# CMM_MACHINE.net
KiCad netlist of a schematic drawn in Altium Designer
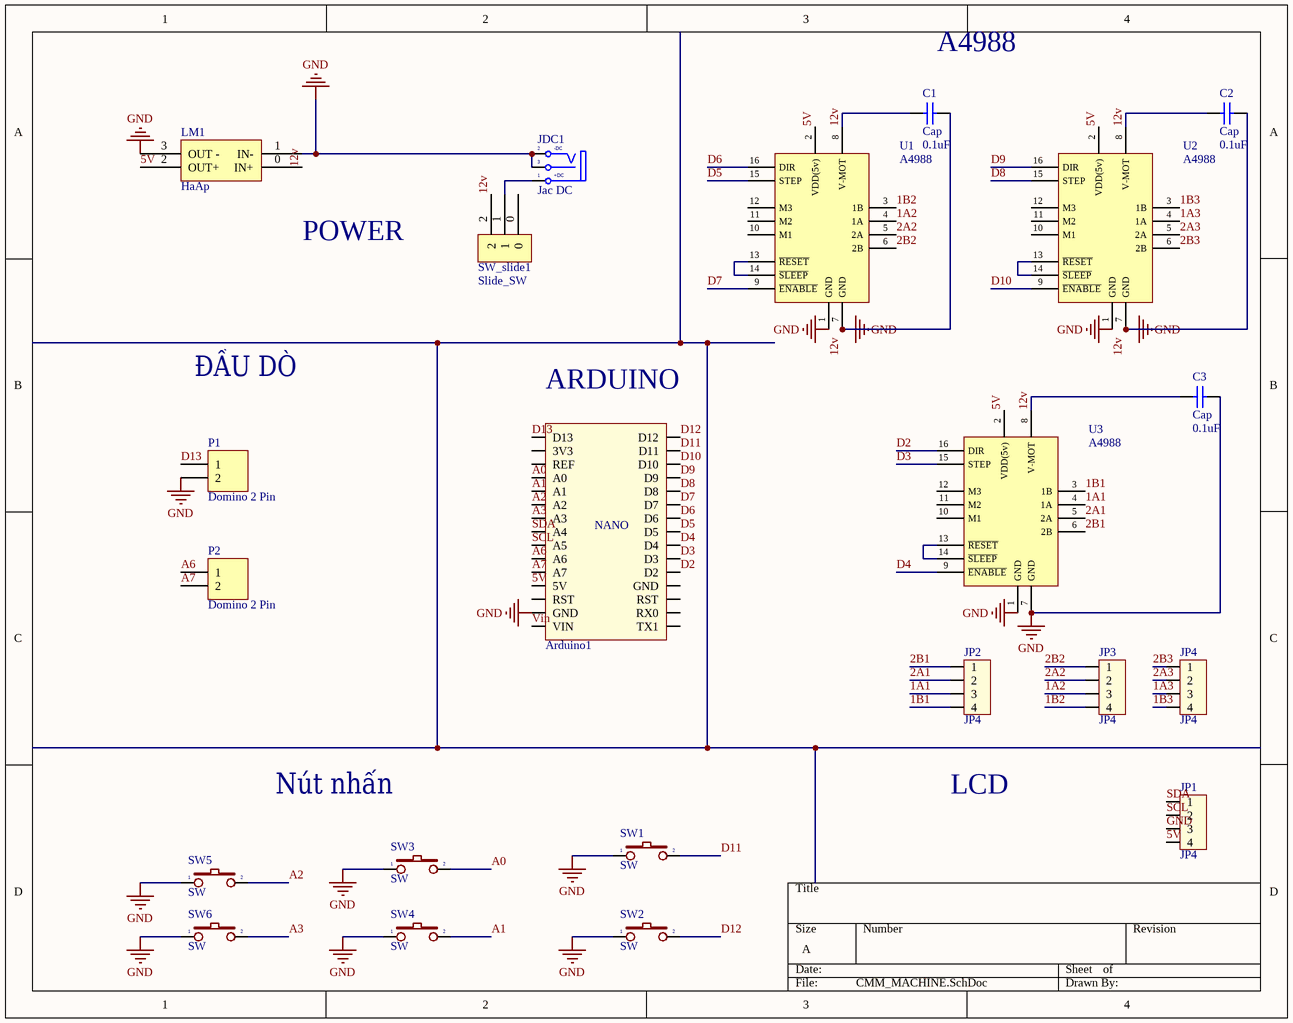
[diagram p0: CMM_MACHINE.SchDoc]

(export (version "E")
  (design (tool "Eeschema 10.0.6"))
  (components
    (comp (ref "Arduino1")
      (value "Arduino Nano")
      (footprint "Arduino Nano")
      (description "Arduino NANO")
      (libsource (lib "TechMT.VN_Lib_Project v2") (part "Arduino Nano"))
    )
    (comp (ref "C1")
      (value "Cap")
      (footprint "C3MM")
      (description "Capacitor")
      (fields (field (name "ALTIUM_VALUE") "0.1uF") (field (name "PUBLISHER") "Altium Limited"))
      (libsource (lib "hphonglib") (part "Cap"))
    )
    (comp (ref "C2")
      (value "Cap")
      (footprint "C3MM")
      (description "Capacitor")
      (fields (field (name "ALTIUM_VALUE") "0.1uF") (field (name "PUBLISHER") "Altium Limited"))
      (libsource (lib "hphonglib") (part "Cap"))
    )
    (comp (ref "C3")
      (value "Cap")
      (footprint "C3MM")
      (description "Capacitor")
      (fields (field (name "ALTIUM_VALUE") "0.1uF") (field (name "PUBLISHER") "Altium Limited"))
      (libsource (lib "hphonglib") (part "Cap"))
    )
    (comp (ref "JDC1")
      (value "Jac DC")
      (footprint "DC0")
      (description "Jac DC input")
      (libsource (lib "TechMT.VN_Lib_Project v2") (part "DCIN"))
    )
    (comp (ref "JP1")
      (value "JP4")
      (footprint "CON4")
      (description "Connector 4")
      (libsource (lib "hphonglib") (part "Con4"))
    )
    (comp (ref "JP2")
      (value "JP4")
      (footprint "CON4")
      (description "Connector 4")
      (libsource (lib "My Library") (part "Con4"))
    )
    (comp (ref "JP3")
      (value "JP4")
      (footprint "CON4")
      (description "Connector 4")
      (libsource (lib "My Library") (part "Con4"))
    )
    (comp (ref "JP4")
      (value "JP4")
      (footprint "CON4")
      (description "Connector 4")
      (libsource (lib "My Library") (part "Con4"))
    )
    (comp (ref "LM1")
      (value "HaAp")
      (footprint "BUCK_LM2596")
      (libsource (lib "BUCK_LM2596") (part "BUCK_LM2596"))
    )
    (comp (ref "P1")
      (value "Domino 2 Pin")
      (footprint "DOMINO_2PIN_5.08mm")
      (libsource (lib "MinhTien_SCHLib") (part "Domino 2 pin"))
    )
    (comp (ref "P2")
      (value "Domino 2 Pin")
      (footprint "DOMINO_2PIN_5.08mm")
      (libsource (lib "MinhTien_SCHLib") (part "Domino 2 pin"))
    )
    (comp (ref "SW1")
      (value "SW")
      (footprint "SW2")
      (description "Switch button 2 pin")
      (libsource (lib "hphonglib") (part "SW2"))
    )
    (comp (ref "SW2")
      (value "SW")
      (footprint "SW2")
      (description "Switch button 2 pin")
      (libsource (lib "hphonglib") (part "SW2"))
    )
    (comp (ref "SW3")
      (value "SW")
      (footprint "SW2")
      (description "Switch button 2 pin")
      (libsource (lib "hphonglib") (part "SW2"))
    )
    (comp (ref "SW4")
      (value "SW")
      (footprint "SW2")
      (description "Switch button 2 pin")
      (libsource (lib "hphonglib") (part "SW2"))
    )
    (comp (ref "SW5")
      (value "SW")
      (footprint "SW2")
      (description "Switch button 2 pin")
      (libsource (lib "hphonglib") (part "SW2"))
    )
    (comp (ref "SW6")
      (value "SW")
      (footprint "SW2")
      (description "Switch button 2 pin")
      (libsource (lib "hphonglib") (part "SW2"))
    )
    (comp (ref "SW_slide1")
      (value "Slide_SW")
      (footprint "Slide_SW")
      (libsource (lib "Cong_tac_truot") (part "Slide_SW"))
    )
    (comp (ref "U1")
      (value "A4988")
      (footprint "A4988(driver)")
      (libsource (lib "My Library") (part "A4988"))
    )
    (comp (ref "U2")
      (value "A4988")
      (footprint "A4988(driver)")
      (libsource (lib "My Library") (part "A4988"))
    )
    (comp (ref "U3")
      (value "A4988")
      (footprint "A4988(driver)")
      (libsource (lib "My Library") (part "A4988"))
    )
  )
  (nets
    (net (code "1") (name "/1A1") (class "Default")
      (node (ref "JP2") (pin "3") (pinfunction "3_3") (pintype "passive"))
      (node (ref "U3") (pin "4") (pinfunction "1A_4") (pintype "power_in"))
    )
    (net (code "2") (name "/1A2") (class "Default")
      (node (ref "JP3") (pin "3") (pinfunction "3_3") (pintype "passive"))
      (node (ref "U1") (pin "4") (pinfunction "1A_4") (pintype "power_in"))
    )
    (net (code "3") (name "/1A3") (class "Default")
      (node (ref "JP4") (pin "3") (pinfunction "3_3") (pintype "passive"))
      (node (ref "U2") (pin "4") (pinfunction "1A_4") (pintype "power_in"))
    )
    (net (code "4") (name "/1B1") (class "Default")
      (node (ref "JP2") (pin "4") (pinfunction "4_4") (pintype "passive"))
      (node (ref "U3") (pin "3") (pinfunction "1B_3") (pintype "power_in"))
    )
    (net (code "5") (name "/1B2") (class "Default")
      (node (ref "JP3") (pin "4") (pinfunction "4_4") (pintype "passive"))
      (node (ref "U1") (pin "3") (pinfunction "1B_3") (pintype "power_in"))
    )
    (net (code "6") (name "/1B3") (class "Default")
      (node (ref "JP4") (pin "4") (pinfunction "4_4") (pintype "passive"))
      (node (ref "U2") (pin "3") (pinfunction "1B_3") (pintype "power_in"))
    )
    (net (code "7") (name "/2A1") (class "Default")
      (node (ref "JP2") (pin "2") (pinfunction "2_2") (pintype "passive"))
      (node (ref "U3") (pin "5") (pinfunction "2A_5") (pintype "power_in"))
    )
    (net (code "8") (name "/2A2") (class "Default")
      (node (ref "JP3") (pin "2") (pinfunction "2_2") (pintype "passive"))
      (node (ref "U1") (pin "5") (pinfunction "2A_5") (pintype "power_in"))
    )
    (net (code "9") (name "/2A3") (class "Default")
      (node (ref "JP4") (pin "2") (pinfunction "2_2") (pintype "passive"))
      (node (ref "U2") (pin "5") (pinfunction "2A_5") (pintype "power_in"))
    )
    (net (code "10") (name "/2B1") (class "Default")
      (node (ref "JP2") (pin "1") (pinfunction "1_1") (pintype "passive"))
      (node (ref "U3") (pin "6") (pinfunction "2B_6") (pintype "power_in"))
    )
    (net (code "11") (name "/2B2") (class "Default")
      (node (ref "JP3") (pin "1") (pinfunction "1_1") (pintype "passive"))
      (node (ref "U1") (pin "6") (pinfunction "2B_6") (pintype "power_in"))
    )
    (net (code "12") (name "/2B3") (class "Default")
      (node (ref "JP4") (pin "1") (pinfunction "1_1") (pintype "passive"))
      (node (ref "U2") (pin "6") (pinfunction "2B_6") (pintype "power_in"))
    )
    (net (code "13") (name "/5V") (class "Default")
      (node (ref "Arduino1") (pin "5V") (pinfunction "5V_5V") (pintype "passive"))
      (node (ref "JP1") (pin "4") (pinfunction "4_4") (pintype "passive"))
      (node (ref "LM1") (pin "2") (pinfunction "OUT+_2") (pintype "passive"))
      (node (ref "U1") (pin "2") (pinfunction "VDD(5v)_2") (pintype "power_in"))
      (node (ref "U2") (pin "2") (pinfunction "VDD(5v)_2") (pintype "power_in"))
      (node (ref "U3") (pin "2") (pinfunction "VDD(5v)_2") (pintype "power_in"))
    )
    (net (code "14") (name "/12v") (class "Default")
      (node (ref "C1") (pin "2") (pinfunction "2_2") (pintype "passive"))
      (node (ref "C2") (pin "2") (pinfunction "2_2") (pintype "passive"))
      (node (ref "C3") (pin "2") (pinfunction "2_2") (pintype "passive"))
      (node (ref "LM1") (pin "0") (pinfunction "IN+_0") (pintype "passive"))
      (node (ref "SW_slide1") (pin "2") (pinfunction "2_2") (pintype "passive"))
      (node (ref "U1") (pin "8") (pinfunction "V-MOT_8") (pintype "power_in"))
      (node (ref "U2") (pin "8") (pinfunction "V-MOT_8") (pintype "power_in"))
      (node (ref "U3") (pin "8") (pinfunction "V-MOT_8") (pintype "power_in"))
    )
    (net (code "15") (name "/A0") (class "Default")
      (node (ref "Arduino1") (pin "A0") (pinfunction "A0_A0") (pintype "passive"))
      (node (ref "SW3") (pin "2") (pinfunction "2_2") (pintype "passive"))
    )
    (net (code "16") (name "/A1") (class "Default")
      (node (ref "Arduino1") (pin "A1") (pinfunction "A1_A1") (pintype "passive"))
      (node (ref "SW4") (pin "2") (pinfunction "2_2") (pintype "passive"))
    )
    (net (code "17") (name "/A2") (class "Default")
      (node (ref "Arduino1") (pin "A2") (pinfunction "A2_A2") (pintype "passive"))
      (node (ref "SW5") (pin "2") (pinfunction "2_2") (pintype "passive"))
    )
    (net (code "18") (name "/A3") (class "Default")
      (node (ref "Arduino1") (pin "A3") (pinfunction "A3_A3") (pintype "passive"))
      (node (ref "SW6") (pin "2") (pinfunction "2_2") (pintype "passive"))
    )
    (net (code "19") (name "/A6") (class "Default")
      (node (ref "Arduino1") (pin "A6") (pinfunction "A6_A6") (pintype "passive"))
      (node (ref "P2") (pin "1") (pinfunction "1_1") (pintype "passive"))
    )
    (net (code "20") (name "/A7") (class "Default")
      (node (ref "Arduino1") (pin "A7") (pinfunction "A7_A7") (pintype "passive"))
      (node (ref "P2") (pin "2") (pinfunction "2_2") (pintype "passive"))
    )
    (net (code "21") (name "/D2") (class "Default")
      (node (ref "Arduino1") (pin "D2") (pinfunction "D2_D2") (pintype "passive"))
      (node (ref "U3") (pin "16") (pinfunction "DIR_16") (pintype "power_in"))
    )
    (net (code "22") (name "/D3") (class "Default")
      (node (ref "Arduino1") (pin "D3") (pinfunction "D3_D3") (pintype "passive"))
      (node (ref "U3") (pin "15") (pinfunction "STEP_15") (pintype "power_in"))
    )
    (net (code "23") (name "/D4") (class "Default")
      (node (ref "Arduino1") (pin "D4") (pinfunction "D4_D4") (pintype "passive"))
      (node (ref "U3") (pin "9") (pinfunction "~{ENABLE}_9") (pintype "power_in"))
    )
    (net (code "24") (name "/D5") (class "Default")
      (node (ref "Arduino1") (pin "D5") (pinfunction "D5_D5") (pintype "passive"))
      (node (ref "U1") (pin "15") (pinfunction "STEP_15") (pintype "power_in"))
    )
    (net (code "25") (name "/D6") (class "Default")
      (node (ref "Arduino1") (pin "D6") (pinfunction "D6_D6") (pintype "passive"))
      (node (ref "U1") (pin "16") (pinfunction "DIR_16") (pintype "power_in"))
    )
    (net (code "26") (name "/D7") (class "Default")
      (node (ref "Arduino1") (pin "D7") (pinfunction "D7_D7") (pintype "passive"))
      (node (ref "U1") (pin "9") (pinfunction "~{ENABLE}_9") (pintype "power_in"))
    )
    (net (code "27") (name "/D8") (class "Default")
      (node (ref "Arduino1") (pin "D8") (pinfunction "D8_D8") (pintype "passive"))
      (node (ref "U2") (pin "15") (pinfunction "STEP_15") (pintype "power_in"))
    )
    (net (code "28") (name "/D9") (class "Default")
      (node (ref "Arduino1") (pin "D9") (pinfunction "D9_D9") (pintype "passive"))
      (node (ref "U2") (pin "16") (pinfunction "DIR_16") (pintype "power_in"))
    )
    (net (code "29") (name "/D10") (class "Default")
      (node (ref "Arduino1") (pin "D10") (pinfunction "D10_D10") (pintype "passive"))
      (node (ref "U2") (pin "9") (pinfunction "~{ENABLE}_9") (pintype "power_in"))
    )
    (net (code "30") (name "/D11") (class "Default")
      (node (ref "Arduino1") (pin "D11") (pinfunction "D11_D11") (pintype "passive"))
      (node (ref "SW1") (pin "2") (pinfunction "2_2") (pintype "passive"))
    )
    (net (code "31") (name "/D12") (class "Default")
      (node (ref "Arduino1") (pin "D12") (pinfunction "D12_D12") (pintype "passive"))
      (node (ref "SW2") (pin "2") (pinfunction "2_2") (pintype "passive"))
    )
    (net (code "32") (name "/D13") (class "Default")
      (node (ref "Arduino1") (pin "D13") (pinfunction "D13_D13") (pintype "passive"))
      (node (ref "P1") (pin "1") (pinfunction "1_1") (pintype "passive"))
    )
    (net (code "33") (name "/SCL") (class "Default")
      (node (ref "Arduino1") (pin "A5") (pinfunction "A5_A5") (pintype "passive"))
      (node (ref "JP1") (pin "2") (pinfunction "2_2") (pintype "passive"))
    )
    (net (code "34") (name "/SDA") (class "Default")
      (node (ref "Arduino1") (pin "A4") (pinfunction "A4_A4") (pintype "passive"))
      (node (ref "JP1") (pin "1") (pinfunction "1_1") (pintype "passive"))
    )
    (net (code "35") (name "/Vin") (class "Default")
      (node (ref "Arduino1") (pin "VIN") (pinfunction "VIN_VIN") (pintype "passive"))
    )
    (net (code "36") (name "GND") (class "Default")
      (node (ref "Arduino1") (pin "GND") (pinfunction "GND_GND") (pintype "passive"))
      (node (ref "C1") (pin "1") (pinfunction "1_1") (pintype "passive"))
      (node (ref "C2") (pin "1") (pinfunction "1_1") (pintype "passive"))
      (node (ref "C3") (pin "1") (pinfunction "1_1") (pintype "passive"))
      (node (ref "JDC1") (pin "2") (pinfunction "TN_2") (pintype "passive"))
      (node (ref "JDC1") (pin "3") (pinfunction "S_3") (pintype "power_in"))
      (node (ref "JP1") (pin "3") (pinfunction "3_3") (pintype "passive"))
      (node (ref "LM1") (pin "1") (pinfunction "IN-_1") (pintype "passive"))
      (node (ref "LM1") (pin "3") (pinfunction "OUT_-_3") (pintype "passive"))
      (node (ref "P1") (pin "2") (pinfunction "2_2") (pintype "passive"))
      (node (ref "SW1") (pin "1") (pinfunction "1_1") (pintype "passive"))
      (node (ref "SW2") (pin "1") (pinfunction "1_1") (pintype "passive"))
      (node (ref "SW3") (pin "1") (pinfunction "1_1") (pintype "passive"))
      (node (ref "SW4") (pin "1") (pinfunction "1_1") (pintype "passive"))
      (node (ref "SW5") (pin "1") (pinfunction "1_1") (pintype "passive"))
      (node (ref "SW6") (pin "1") (pinfunction "1_1") (pintype "passive"))
      (node (ref "U1") (pin "1") (pinfunction "GND_1") (pintype "power_in"))
      (node (ref "U1") (pin "7") (pinfunction "GND_7") (pintype "power_in"))
      (node (ref "U2") (pin "1") (pinfunction "GND_1") (pintype "power_in"))
      (node (ref "U2") (pin "7") (pinfunction "GND_7") (pintype "power_in"))
      (node (ref "U3") (pin "1") (pinfunction "GND_1") (pintype "power_in"))
      (node (ref "U3") (pin "7") (pinfunction "GND_7") (pintype "power_in"))
    )
    (net (code "37") (name "Net-(JDC1-T)") (class "Default")
      (node (ref "JDC1") (pin "1") (pinfunction "T_1") (pintype "passive"))
      (node (ref "SW_slide1") (pin "1") (pinfunction "1_1") (pintype "passive"))
    )
    (net (code "38") (name "Net-(U1-~{RESET})") (class "Default")
      (node (ref "U1") (pin "13") (pinfunction "~{RESET}_13") (pintype "power_in"))
      (node (ref "U1") (pin "14") (pinfunction "~{SLEEP}_14") (pintype "power_in"))
    )
    (net (code "39") (name "Net-(U2-~{RESET})") (class "Default")
      (node (ref "U2") (pin "13") (pinfunction "~{RESET}_13") (pintype "power_in"))
      (node (ref "U2") (pin "14") (pinfunction "~{SLEEP}_14") (pintype "power_in"))
    )
    (net (code "40") (name "Net-(U3-~{RESET})") (class "Default")
      (node (ref "U3") (pin "13") (pinfunction "~{RESET}_13") (pintype "power_in"))
      (node (ref "U3") (pin "14") (pinfunction "~{SLEEP}_14") (pintype "power_in"))
    )
    (net (code "41") (name "unconnected-(Arduino1-Pad3V3)") (class "Default")
      (node (ref "Arduino1") (pin "3V3") (pinfunction "3V3_3V3") (pintype "passive"))
    )
    (net (code "42") (name "unconnected-(Arduino1-PadGND)") (class "Default")
      (node (ref "Arduino1") (pin "GND") (pinfunction "GND_GND") (pintype "passive"))
    )
    (net (code "43") (name "unconnected-(Arduino1-PadREF)") (class "Default")
      (node (ref "Arduino1") (pin "REF") (pinfunction "REF_REF") (pintype "passive"))
    )
    (net (code "44") (name "unconnected-(Arduino1-PadRST)") (class "Default")
      (node (ref "Arduino1") (pin "RST") (pinfunction "RST_RST") (pintype "passive"))
    )
    (net (code "45") (name "unconnected-(Arduino1-PadRST)_1") (class "Default")
      (node (ref "Arduino1") (pin "RST") (pinfunction "RST_RST") (pintype "passive"))
    )
    (net (code "46") (name "unconnected-(Arduino1-PadRX0)") (class "Default")
      (node (ref "Arduino1") (pin "RX0") (pinfunction "RX0_RX0") (pintype "passive"))
    )
    (net (code "47") (name "unconnected-(Arduino1-PadTX1)") (class "Default")
      (node (ref "Arduino1") (pin "TX1") (pinfunction "TX1_TX1") (pintype "passive"))
    )
    (net (code "48") (name "unconnected-(SW_slide1-Pad0)") (class "Default")
      (node (ref "SW_slide1") (pin "0") (pinfunction "0_0") (pintype "passive"))
    )
    (net (code "49") (name "unconnected-(U1-M1-Pad10)") (class "Default")
      (node (ref "U1") (pin "10") (pinfunction "M1_10") (pintype "power_in"))
    )
    (net (code "50") (name "unconnected-(U1-M2-Pad11)") (class "Default")
      (node (ref "U1") (pin "11") (pinfunction "M2_11") (pintype "power_in"))
    )
    (net (code "51") (name "unconnected-(U1-M3-Pad12)") (class "Default")
      (node (ref "U1") (pin "12") (pinfunction "M3_12") (pintype "power_in"))
    )
    (net (code "52") (name "unconnected-(U2-M1-Pad10)") (class "Default")
      (node (ref "U2") (pin "10") (pinfunction "M1_10") (pintype "power_in"))
    )
    (net (code "53") (name "unconnected-(U2-M2-Pad11)") (class "Default")
      (node (ref "U2") (pin "11") (pinfunction "M2_11") (pintype "power_in"))
    )
    (net (code "54") (name "unconnected-(U2-M3-Pad12)") (class "Default")
      (node (ref "U2") (pin "12") (pinfunction "M3_12") (pintype "power_in"))
    )
    (net (code "55") (name "unconnected-(U3-M1-Pad10)") (class "Default")
      (node (ref "U3") (pin "10") (pinfunction "M1_10") (pintype "power_in"))
    )
    (net (code "56") (name "unconnected-(U3-M2-Pad11)") (class "Default")
      (node (ref "U3") (pin "11") (pinfunction "M2_11") (pintype "power_in"))
    )
    (net (code "57") (name "unconnected-(U3-M3-Pad12)") (class "Default")
      (node (ref "U3") (pin "12") (pinfunction "M3_12") (pintype "power_in"))
    )
  )
)
